# ESP8266V3.net
KiCad netlist of a schematic drawn in Altium Designer
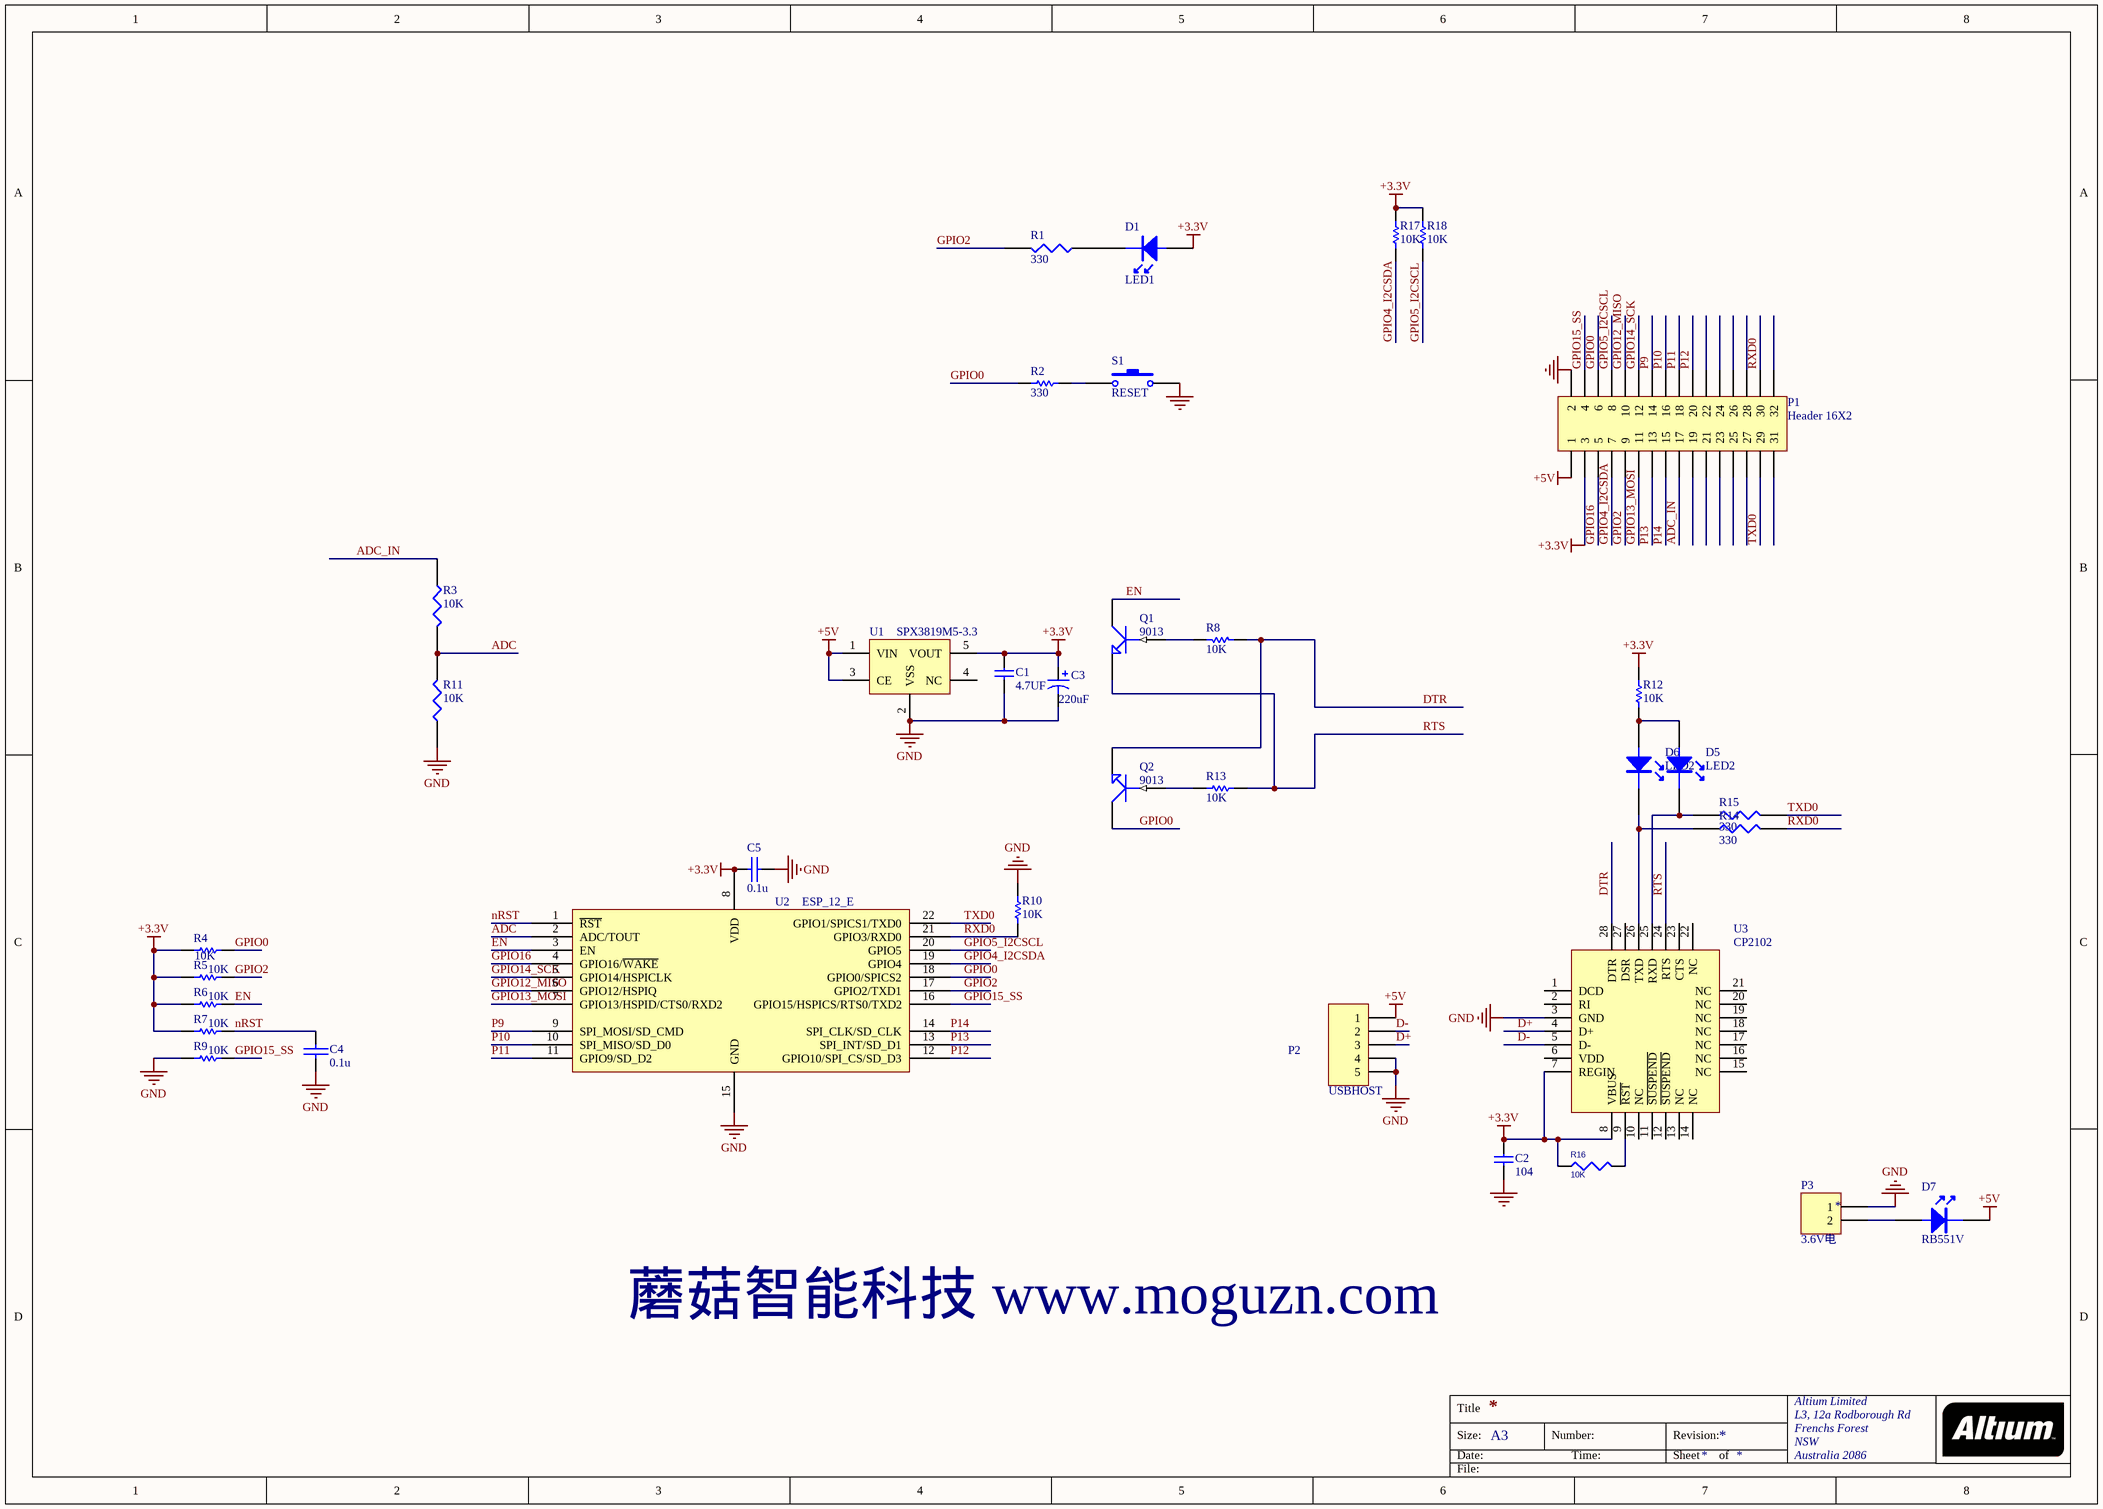
[diagram p0: ESP8266V3.SchDoc]

(export (version "E")
  (design (tool "Eeschema 10.0.6"))
  (components
    (comp (ref "C1")
      (value "4.7UF")
      (footprint "0805C1")
      (description "Capacitor, NP0, ?.1pF")
      (fields (field (name "PART NUMBER") "C0402-1.2p") (field (name "PUBLISHER") "Nordic Semiconductor"))
      (libsource (lib "Nordic Passive DB") (part "CAP"))
    )
    (comp (ref "C2")
      (value "104")
      (footprint "0603CC")
      (description "Capacitor, NP0, ?.1pF")
      (fields (field (name "PART NUMBER") "C0402-1.2p") (field (name "PUBLISHER") "Nordic Semiconductor"))
      (libsource (lib "Nordic Passive DB") (part "CAP"))
    )
    (comp (ref "C3")
      (value "220uF")
      (footprint "CAP-6032")
      (description "Polarized Capacitor (Radial)")
      (fields (field (name "Comment") "Cap Pol1") (field (name "PUBLISHER") "Altium Limited"))
      (libsource (lib "Miscellaneous Devices") (part "Cap Pol1"))
    )
    (comp (ref "C4")
      (value "0.1u")
      (footprint "0603CC")
      (description "Capacitor")
      (libsource (lib "*") (part "CAP"))
    )
    (comp (ref "C5")
      (value "0.1u")
      (footprint "0603CC")
      (description "Capacitor")
      (libsource (lib "*") (part "CAP"))
    )
    (comp (ref "D1") (value "LED1") (footprint "0805LED") (libsource (lib "*") (part "LED")))
    (comp (ref "D5") (value "LED2") (footprint "0805LED") (libsource (lib "*") (part "LED")))
    (comp (ref "D6") (value "LED2") (footprint "0805LED") (libsource (lib "*") (part "LED")))
    (comp (ref "D7") (value "RB551V") (footprint "0805LED") (libsource (lib "*") (part "LED")))
    (comp (ref "P1")
      (value "Header 16X2")
      (footprint "HEADER 2*5")
      (description "Header, 16-Pin, Dual row")
      (fields (field (name "PUBLISHER") "Altium Limited"))
      (libsource (lib "Miscellaneous Connectors") (part "Header 16X2"))
    )
    (comp (ref "P2")
      (value "USBHOST")
      (footprint "USB_mini")
      (description "Header, 5-Pin")
      (fields (field (name "PUBLISHER") "Altium Limited"))
      (libsource (lib "Miscellaneous Connectors") (part "Header 5"))
    )
    (comp (ref "P3")
      (value "*")
      (footprint "lithium_connector")
      (description "Header, 2-Pin")
      (fields (field (name "ALTIUM_UNNAMED_1") "3.6V电") (field (name "PUBLISHER") "Altium Limited"))
      (libsource (lib "Miscellaneous Connectors") (part "Header 2"))
    )
    (comp (ref "Q1")
      (value "9013")
      (footprint "SOT-23")
      (description "NPN Transistor")
      (libsource (lib "*") (part "NPN1"))
    )
    (comp (ref "Q2")
      (value "9013")
      (footprint "SOT-23")
      (description "NPN Transistor")
      (libsource (lib "*") (part "NPN1"))
    )
    (comp (ref "R1") (value "330") (footprint "0603RR") (libsource (lib "*") (part "RES1")))
    (comp (ref "R2")
      (value "330")
      (footprint "0603RR")
      (description "Resistor")
      (fields (field (name "Comment") "Res1") (field (name "PUBLISHER") "Altium Limited"))
      (libsource (lib "Miscellaneous Devices") (part "Res1"))
    )
    (comp (ref "R3") (value "10K") (footprint "0603RR") (libsource (lib "*") (part "RES1")))
    (comp (ref "R4")
      (value "10K")
      (footprint "0603RR")
      (description "Resistor")
      (fields (field (name "Comment") "Res1") (field (name "PUBLISHER") "Altium Limited"))
      (libsource (lib "Miscellaneous Devices") (part "Res1"))
    )
    (comp (ref "R5")
      (value "10K")
      (footprint "0603RR")
      (description "Resistor")
      (fields (field (name "Comment") "Res1") (field (name "PUBLISHER") "Altium Limited"))
      (libsource (lib "Miscellaneous Devices") (part "Res1"))
    )
    (comp (ref "R6")
      (value "10K")
      (footprint "0603RR")
      (description "Resistor")
      (fields (field (name "Comment") "Res1") (field (name "PUBLISHER") "Altium Limited"))
      (libsource (lib "Miscellaneous Devices") (part "Res1"))
    )
    (comp (ref "R7")
      (value "10K")
      (footprint "0603RR")
      (description "Resistor")
      (fields (field (name "Comment") "Res1") (field (name "PUBLISHER") "Altium Limited"))
      (libsource (lib "Miscellaneous Devices") (part "Res1"))
    )
    (comp (ref "R8")
      (value "10K")
      (footprint "0603RR")
      (description "Semiconductor Resistor")
      (fields (field (name "Comment") "Res Semi") (field (name "PUBLISHER") "Altium Limited"))
      (libsource (lib "Miscellaneous Devices") (part "Res Semi"))
    )
    (comp (ref "R9")
      (value "10K")
      (footprint "0603RR")
      (description "Resistor")
      (fields (field (name "Comment") "Res1") (field (name "PUBLISHER") "Altium Limited"))
      (libsource (lib "Miscellaneous Devices") (part "Res1"))
    )
    (comp (ref "R10")
      (value "10K")
      (footprint "0603RR")
      (description "Resistor")
      (fields (field (name "Comment") "Res1") (field (name "PUBLISHER") "Altium Limited"))
      (libsource (lib "Miscellaneous Devices") (part "Res1"))
    )
    (comp (ref "R11") (value "10K") (footprint "0603RR") (libsource (lib "*") (part "RES1")))
    (comp (ref "R12")
      (value "10K")
      (footprint "0603RR")
      (description "Semiconductor Resistor")
      (fields (field (name "Comment") "Res Semi") (field (name "PUBLISHER") "Altium Limited"))
      (libsource (lib "Miscellaneous Devices") (part "Res Semi"))
    )
    (comp (ref "R13")
      (value "10K")
      (footprint "0603RR")
      (description "Resistor")
      (fields (field (name "Comment") "Res1") (field (name "PUBLISHER") "Altium Limited"))
      (libsource (lib "Miscellaneous Devices") (part "Res1"))
    )
    (comp (ref "R14") (value "330") (footprint "0603RR") (libsource (lib "*") (part "RES1")))
    (comp (ref "R15") (value "330") (footprint "0603RR") (libsource (lib "*") (part "RES1")))
    (comp (ref "R16") (value "10K") (footprint "0603RR") (libsource (lib "*") (part "R_0402")))
    (comp (ref "R17")
      (value "10K")
      (footprint "0603RR")
      (description "Resistor")
      (fields (field (name "Comment") "Res1") (field (name "PUBLISHER") "Altium Limited"))
      (libsource (lib "Miscellaneous Devices") (part "Res1"))
    )
    (comp (ref "R18")
      (value "10K")
      (footprint "0603RR")
      (description "Semiconductor Resistor")
      (fields (field (name "Comment") "Res Semi") (field (name "PUBLISHER") "Altium Limited"))
      (libsource (lib "Miscellaneous Devices") (part "Res Semi"))
    )
    (comp (ref "S1")
      (value "RESET")
      (footprint "KEY_6*6*X _SMT")
      (description "Switch")
      (fields (field (name "PUBLISHER") "Altium Limited"))
      (libsource (lib "Miscellaneous Devices") (part "SW-PB"))
    )
    (comp (ref "U1") (value "SPX3819M5-3.3") (footprint "SOT23-5") (libsource (lib "hhic") (part "XC6215")))
    (comp (ref "U2")
      (value "ESP_12_E")
      (footprint "ESP_12_E")
      (description "ESP-12 Wi-Fi Module by AI-Thinker")
      (libsource (lib "ESP-12") (part "ESP_12_E"))
    )
    (comp (ref "U3") (value "CP2102") (footprint "QFN28") (libsource (lib "hhic") (part "CP2102")))
  )
  (nets
    (net (code "1") (name "+3.3V") (class "Default")
      (node (ref "C1") (pin "1") (pinfunction "1_1") (pintype "passive"))
      (node (ref "C2") (pin "1") (pinfunction "1_1") (pintype "passive"))
      (node (ref "C3") (pin "1") (pinfunction "1_1") (pintype "passive"))
      (node (ref "C5") (pin "2") (pinfunction "2_2") (pintype "passive"))
      (node (ref "D1") (pin "1") (pinfunction "1_1") (pintype "passive"))
      (node (ref "P1") (pin "3") (pinfunction "3_3") (pintype "passive"))
      (node (ref "R12") (pin "1") (pinfunction "1_1") (pintype "passive"))
      (node (ref "R16") (pin "1") (pinfunction "1_1") (pintype "passive"))
      (node (ref "R17") (pin "2") (pinfunction "2_2") (pintype "passive"))
      (node (ref "R18") (pin "2") (pinfunction "2_2") (pintype "passive"))
      (node (ref "R4") (pin "2") (pinfunction "2_2") (pintype "passive"))
      (node (ref "R5") (pin "2") (pinfunction "2_2") (pintype "passive"))
      (node (ref "R6") (pin "2") (pinfunction "2_2") (pintype "passive"))
      (node (ref "R7") (pin "2") (pinfunction "2_2") (pintype "passive"))
      (node (ref "U1") (pin "5") (pinfunction "VOUT_5") (pintype "passive"))
      (node (ref "U2") (pin "8") (pinfunction "VDD_8") (pintype "passive"))
      (node (ref "U3") (pin "7") (pinfunction "REGIN_7") (pintype "passive"))
      (node (ref "U3") (pin "8") (pinfunction "VBUS_8") (pintype "passive"))
    )
    (net (code "2") (name "+5V") (class "Default")
      (node (ref "D7") (pin "2") (pinfunction "2_2") (pintype "passive"))
      (node (ref "P1") (pin "1") (pinfunction "1_1") (pintype "passive"))
      (node (ref "P2") (pin "1") (pinfunction "1_1") (pintype "passive"))
      (node (ref "U1") (pin "1") (pinfunction "VIN_1") (pintype "passive"))
      (node (ref "U1") (pin "3") (pinfunction "CE_3") (pintype "passive"))
    )
    (net (code "3") (name "/ADC") (class "Default")
      (node (ref "R11") (pin "2") (pinfunction "2_2") (pintype "passive"))
      (node (ref "R3") (pin "2") (pinfunction "2_2") (pintype "passive"))
      (node (ref "U2") (pin "2") (pinfunction "ADC/TOUT_2") (pintype "passive"))
    )
    (net (code "4") (name "/ADC_IN") (class "Default")
      (node (ref "P1") (pin "17") (pinfunction "17_17") (pintype "passive"))
      (node (ref "R3") (pin "1") (pinfunction "1_1") (pintype "passive"))
    )
    (net (code "5") (name "/D+") (class "Default")
      (node (ref "P2") (pin "3") (pinfunction "3_3") (pintype "passive"))
      (node (ref "U3") (pin "4") (pinfunction "D+_4") (pintype "passive"))
    )
    (net (code "6") (name "/D-") (class "Default")
      (node (ref "P2") (pin "2") (pinfunction "2_2") (pintype "passive"))
      (node (ref "U3") (pin "5") (pinfunction "D-_5") (pintype "passive"))
    )
    (net (code "7") (name "/DTR") (class "Default")
      (node (ref "Q2") (pin "2") (pinfunction "E_2") (pintype "passive"))
      (node (ref "R8") (pin "1") (pinfunction "1_1") (pintype "passive"))
      (node (ref "U3") (pin "28") (pinfunction "DTR_28") (pintype "passive"))
    )
    (net (code "8") (name "/EN") (class "Default")
      (node (ref "Q1") (pin "3") (pinfunction "C_3") (pintype "passive"))
      (node (ref "R6") (pin "1") (pinfunction "1_1") (pintype "passive"))
      (node (ref "U2") (pin "3") (pinfunction "EN_3") (pintype "passive"))
    )
    (net (code "9") (name "/GPIO0") (class "Default")
      (node (ref "P1") (pin "6") (pinfunction "6_6") (pintype "passive"))
      (node (ref "Q2") (pin "3") (pinfunction "C_3") (pintype "passive"))
      (node (ref "R2") (pin "1") (pinfunction "1_1") (pintype "passive"))
      (node (ref "R4") (pin "1") (pinfunction "1_1") (pintype "passive"))
      (node (ref "U2") (pin "18") (pinfunction "GPIO0/SPICS2_18") (pintype "passive"))
    )
    (net (code "10") (name "/GPIO2") (class "Default")
      (node (ref "P1") (pin "9") (pinfunction "9_9") (pintype "passive"))
      (node (ref "R1") (pin "2") (pinfunction "2_2") (pintype "passive"))
      (node (ref "R5") (pin "1") (pinfunction "1_1") (pintype "passive"))
      (node (ref "U2") (pin "17") (pinfunction "GPIO2/TXD1_17") (pintype "passive"))
    )
    (net (code "11") (name "/GPIO4_I2CSDA") (class "Default")
      (node (ref "P1") (pin "7") (pinfunction "7_7") (pintype "passive"))
      (node (ref "R17") (pin "1") (pinfunction "1_1") (pintype "passive"))
      (node (ref "U2") (pin "19") (pinfunction "GPIO4_19") (pintype "passive"))
    )
    (net (code "12") (name "/GPIO5_I2CSCL") (class "Default")
      (node (ref "P1") (pin "8") (pinfunction "8_8") (pintype "passive"))
      (node (ref "R18") (pin "1") (pinfunction "1_1") (pintype "passive"))
      (node (ref "U2") (pin "20") (pinfunction "GPIO5_20") (pintype "passive"))
    )
    (net (code "13") (name "/GPIO12_MISO") (class "Default")
      (node (ref "P1") (pin "10") (pinfunction "10_10") (pintype "passive"))
      (node (ref "U2") (pin "6") (pinfunction "GPIO12/HSPIQ_6") (pintype "passive"))
    )
    (net (code "14") (name "/GPIO13_MOSI") (class "Default")
      (node (ref "P1") (pin "11") (pinfunction "11_11") (pintype "passive"))
      (node (ref "U2") (pin "7") (pinfunction "GPIO13/HSPID/CTS0/RXD2_7") (pintype "passive"))
    )
    (net (code "15") (name "/GPIO14_SCK") (class "Default")
      (node (ref "P1") (pin "12") (pinfunction "12_12") (pintype "passive"))
      (node (ref "U2") (pin "5") (pinfunction "GPIO14/HSPICLK_5") (pintype "passive"))
    )
    (net (code "16") (name "/GPIO15_SS") (class "Default")
      (node (ref "P1") (pin "4") (pinfunction "4_4") (pintype "passive"))
      (node (ref "R9") (pin "1") (pinfunction "1_1") (pintype "passive"))
      (node (ref "U2") (pin "16") (pinfunction "GPIO15/HSPICS/RTS0/TXD2_16") (pintype "passive"))
    )
    (net (code "17") (name "/GPIO16") (class "Default")
      (node (ref "P1") (pin "5") (pinfunction "5_5") (pintype "passive"))
      (node (ref "U2") (pin "4") (pinfunction "GPIO16/~{WAKE}_4") (pintype "passive"))
    )
    (net (code "18") (name "/P9") (class "Default")
      (node (ref "P1") (pin "14") (pinfunction "14_14") (pintype "passive"))
      (node (ref "U2") (pin "9") (pinfunction "SPI_MOSI/SD_CMD_9") (pintype "passive"))
    )
    (net (code "19") (name "/P10") (class "Default")
      (node (ref "P1") (pin "16") (pinfunction "16_16") (pintype "passive"))
      (node (ref "U2") (pin "10") (pinfunction "SPI_MISO/SD_D0_10") (pintype "passive"))
    )
    (net (code "20") (name "/P11") (class "Default")
      (node (ref "P1") (pin "18") (pinfunction "18_18") (pintype "passive"))
      (node (ref "U2") (pin "11") (pinfunction "GPIO9/SD_D2_11") (pintype "passive"))
    )
    (net (code "21") (name "/P12") (class "Default")
      (node (ref "P1") (pin "20") (pinfunction "20_20") (pintype "passive"))
      (node (ref "U2") (pin "12") (pinfunction "GPIO10/SPI_CS/SD_D3_12") (pintype "passive"))
    )
    (net (code "22") (name "/P13") (class "Default")
      (node (ref "P1") (pin "13") (pinfunction "13_13") (pintype "passive"))
      (node (ref "U2") (pin "13") (pinfunction "SPI_INT/SD_D1_13") (pintype "passive"))
    )
    (net (code "23") (name "/P14") (class "Default")
      (node (ref "P1") (pin "15") (pinfunction "15_15") (pintype "passive"))
      (node (ref "U2") (pin "14") (pinfunction "SPI_CLK/SD_CLK_14") (pintype "passive"))
    )
    (net (code "24") (name "/RTS") (class "Default")
      (node (ref "Q1") (pin "2") (pinfunction "E_2") (pintype "passive"))
      (node (ref "R13") (pin "1") (pinfunction "1_1") (pintype "passive"))
      (node (ref "U3") (pin "24") (pinfunction "RTS_24") (pintype "passive"))
    )
    (net (code "25") (name "/RXD0") (class "Default")
      (node (ref "P1") (pin "30") (pinfunction "30_30") (pintype "passive"))
      (node (ref "R10") (pin "2") (pinfunction "2_2") (pintype "passive"))
      (node (ref "R14") (pin "2") (pinfunction "2_2") (pintype "passive"))
      (node (ref "U2") (pin "21") (pinfunction "GPIO3/RXD0_21") (pintype "passive"))
    )
    (net (code "26") (name "/TXD0") (class "Default")
      (node (ref "P1") (pin "29") (pinfunction "29_29") (pintype "passive"))
      (node (ref "R15") (pin "2") (pinfunction "2_2") (pintype "passive"))
      (node (ref "U2") (pin "22") (pinfunction "GPIO1/SPICS1/TXD0_22") (pintype "passive"))
    )
    (net (code "27") (name "/nRST") (class "Default")
      (node (ref "C4") (pin "2") (pinfunction "2_2") (pintype "passive"))
      (node (ref "R7") (pin "1") (pinfunction "1_1") (pintype "passive"))
      (node (ref "U2") (pin "1") (pinfunction "~{RST}_1") (pintype "passive"))
    )
    (net (code "28") (name "GND") (class "Default")
      (node (ref "C1") (pin "2") (pinfunction "2_2") (pintype "passive"))
      (node (ref "C2") (pin "2") (pinfunction "2_2") (pintype "passive"))
      (node (ref "C3") (pin "2") (pinfunction "2_2") (pintype "passive"))
      (node (ref "C4") (pin "1") (pinfunction "1_1") (pintype "passive"))
      (node (ref "C5") (pin "1") (pinfunction "1_1") (pintype "passive"))
      (node (ref "P1") (pin "2") (pinfunction "2_2") (pintype "passive"))
      (node (ref "P2") (pin "4") (pinfunction "4_4") (pintype "passive"))
      (node (ref "P2") (pin "5") (pinfunction "5_5") (pintype "passive"))
      (node (ref "P3") (pin "1") (pinfunction "1_1") (pintype "passive"))
      (node (ref "R10") (pin "1") (pinfunction "1_1") (pintype "passive"))
      (node (ref "R11") (pin "1") (pinfunction "1_1") (pintype "passive"))
      (node (ref "R9") (pin "2") (pinfunction "2_2") (pintype "passive"))
      (node (ref "S1") (pin "1") (pinfunction "1_1") (pintype "passive"))
      (node (ref "U1") (pin "2") (pinfunction "VSS_2") (pintype "passive"))
      (node (ref "U2") (pin "15") (pinfunction "GND_15") (pintype "passive"))
      (node (ref "U3") (pin "3") (pinfunction "GND_3") (pintype "passive"))
    )
    (net (code "29") (name "Net-(D1-Pad2)") (class "Default")
      (node (ref "D1") (pin "2") (pinfunction "2_2") (pintype "passive"))
      (node (ref "R1") (pin "1") (pinfunction "1_1") (pintype "passive"))
    )
    (net (code "30") (name "Net-(D5-Pad1)") (class "Default")
      (node (ref "D5") (pin "1") (pinfunction "1_1") (pintype "passive"))
      (node (ref "D6") (pin "1") (pinfunction "1_1") (pintype "passive"))
      (node (ref "R12") (pin "2") (pinfunction "2_2") (pintype "passive"))
    )
    (net (code "31") (name "Net-(D7-Pad1)") (class "Default")
      (node (ref "D7") (pin "1") (pinfunction "1_1") (pintype "passive"))
      (node (ref "P3") (pin "2") (pinfunction "2_2") (pintype "passive"))
    )
    (net (code "32") (name "Net-(Q1-B)") (class "Default")
      (node (ref "Q1") (pin "1") (pinfunction "B_1") (pintype "input"))
      (node (ref "R8") (pin "2") (pinfunction "2_2") (pintype "passive"))
    )
    (net (code "33") (name "Net-(Q2-B)") (class "Default")
      (node (ref "Q2") (pin "1") (pinfunction "B_1") (pintype "input"))
      (node (ref "R13") (pin "2") (pinfunction "2_2") (pintype "passive"))
    )
    (net (code "34") (name "Net-(R2-Pad2)") (class "Default")
      (node (ref "R2") (pin "2") (pinfunction "2_2") (pintype "passive"))
      (node (ref "S1") (pin "2") (pinfunction "2_2") (pintype "passive"))
    )
    (net (code "35") (name "Net-(U3-RXD)") (class "Default")
      (node (ref "D5") (pin "2") (pinfunction "2_2") (pintype "passive"))
      (node (ref "R15") (pin "1") (pinfunction "1_1") (pintype "passive"))
      (node (ref "U3") (pin "25") (pinfunction "RXD_25") (pintype "passive"))
    )
    (net (code "36") (name "Net-(U3-TXD)") (class "Default")
      (node (ref "D6") (pin "2") (pinfunction "2_2") (pintype "passive"))
      (node (ref "R14") (pin "1") (pinfunction "1_1") (pintype "passive"))
      (node (ref "U3") (pin "26") (pinfunction "TXD_26") (pintype "passive"))
    )
    (net (code "37") (name "Net-(U3-~{RST})") (class "Default")
      (node (ref "R16") (pin "2") (pinfunction "2_2") (pintype "passive"))
      (node (ref "U3") (pin "9") (pinfunction "~{RST}_9") (pintype "passive"))
    )
    (net (code "38") (name "unconnected-(P1-Pad19)") (class "Default")
      (node (ref "P1") (pin "19") (pinfunction "19_19") (pintype "passive"))
    )
    (net (code "39") (name "unconnected-(P1-Pad21)") (class "Default")
      (node (ref "P1") (pin "21") (pinfunction "21_21") (pintype "passive"))
    )
    (net (code "40") (name "unconnected-(P1-Pad22)") (class "Default")
      (node (ref "P1") (pin "22") (pinfunction "22_22") (pintype "passive"))
    )
    (net (code "41") (name "unconnected-(P1-Pad23)") (class "Default")
      (node (ref "P1") (pin "23") (pinfunction "23_23") (pintype "passive"))
    )
    (net (code "42") (name "unconnected-(P1-Pad24)") (class "Default")
      (node (ref "P1") (pin "24") (pinfunction "24_24") (pintype "passive"))
    )
    (net (code "43") (name "unconnected-(P1-Pad25)") (class "Default")
      (node (ref "P1") (pin "25") (pinfunction "25_25") (pintype "passive"))
    )
    (net (code "44") (name "unconnected-(P1-Pad26)") (class "Default")
      (node (ref "P1") (pin "26") (pinfunction "26_26") (pintype "passive"))
    )
    (net (code "45") (name "unconnected-(P1-Pad27)") (class "Default")
      (node (ref "P1") (pin "27") (pinfunction "27_27") (pintype "passive"))
    )
    (net (code "46") (name "unconnected-(P1-Pad28)") (class "Default")
      (node (ref "P1") (pin "28") (pinfunction "28_28") (pintype "passive"))
    )
    (net (code "47") (name "unconnected-(P1-Pad31)") (class "Default")
      (node (ref "P1") (pin "31") (pinfunction "31_31") (pintype "passive"))
    )
    (net (code "48") (name "unconnected-(P1-Pad32)") (class "Default")
      (node (ref "P1") (pin "32") (pinfunction "32_32") (pintype "passive"))
    )
    (net (code "49") (name "unconnected-(U1-NC-Pad4)") (class "Default")
      (node (ref "U1") (pin "4") (pinfunction "NC_4") (pintype "passive"))
    )
    (net (code "50") (name "unconnected-(U3-CTS-Pad23)") (class "Default")
      (node (ref "U3") (pin "23") (pinfunction "CTS_23") (pintype "passive"))
    )
    (net (code "51") (name "unconnected-(U3-DCD-Pad1)") (class "Default")
      (node (ref "U3") (pin "1") (pinfunction "DCD_1") (pintype "passive"))
    )
    (net (code "52") (name "unconnected-(U3-DSR-Pad27)") (class "Default")
      (node (ref "U3") (pin "27") (pinfunction "DSR_27") (pintype "passive"))
    )
    (net (code "53") (name "unconnected-(U3-NC-Pad10)") (class "Default")
      (node (ref "U3") (pin "10") (pinfunction "NC_10") (pintype "passive"))
    )
    (net (code "54") (name "unconnected-(U3-NC-Pad13)") (class "Default")
      (node (ref "U3") (pin "13") (pinfunction "NC_13") (pintype "passive"))
    )
    (net (code "55") (name "unconnected-(U3-NC-Pad14)") (class "Default")
      (node (ref "U3") (pin "14") (pinfunction "NC_14") (pintype "passive"))
    )
    (net (code "56") (name "unconnected-(U3-NC-Pad15)") (class "Default")
      (node (ref "U3") (pin "15") (pinfunction "NC_15") (pintype "passive"))
    )
    (net (code "57") (name "unconnected-(U3-NC-Pad16)") (class "Default")
      (node (ref "U3") (pin "16") (pinfunction "NC_16") (pintype "passive"))
    )
    (net (code "58") (name "unconnected-(U3-NC-Pad17)") (class "Default")
      (node (ref "U3") (pin "17") (pinfunction "NC_17") (pintype "passive"))
    )
    (net (code "59") (name "unconnected-(U3-NC-Pad18)") (class "Default")
      (node (ref "U3") (pin "18") (pinfunction "NC_18") (pintype "passive"))
    )
    (net (code "60") (name "unconnected-(U3-NC-Pad19)") (class "Default")
      (node (ref "U3") (pin "19") (pinfunction "NC_19") (pintype "passive"))
    )
    (net (code "61") (name "unconnected-(U3-NC-Pad20)") (class "Default")
      (node (ref "U3") (pin "20") (pinfunction "NC_20") (pintype "passive"))
    )
    (net (code "62") (name "unconnected-(U3-NC-Pad21)") (class "Default")
      (node (ref "U3") (pin "21") (pinfunction "NC_21") (pintype "passive"))
    )
    (net (code "63") (name "unconnected-(U3-NC-Pad22)") (class "Default")
      (node (ref "U3") (pin "22") (pinfunction "NC_22") (pintype "passive"))
    )
    (net (code "64") (name "unconnected-(U3-RI-Pad2)") (class "Default")
      (node (ref "U3") (pin "2") (pinfunction "RI_2") (pintype "passive"))
    )
    (net (code "65") (name "unconnected-(U3-VDD-Pad6)") (class "Default")
      (node (ref "U3") (pin "6") (pinfunction "VDD_6") (pintype "passive"))
    )
    (net (code "66") (name "unconnected-(U3-~{SUSPEND}-Pad11)") (class "Default")
      (node (ref "U3") (pin "11") (pinfunction "~{SUSPEND}_11") (pintype "passive"))
    )
    (net (code "67") (name "unconnected-(U3-~{SUSPEND}-Pad12)") (class "Default")
      (node (ref "U3") (pin "12") (pinfunction "~{SUSPEND}_12") (pintype "passive"))
    )
  )
)
